# CANdiy-FD-Shield_v11.net
KiCad netlist of a schematic drawn in EAGLE
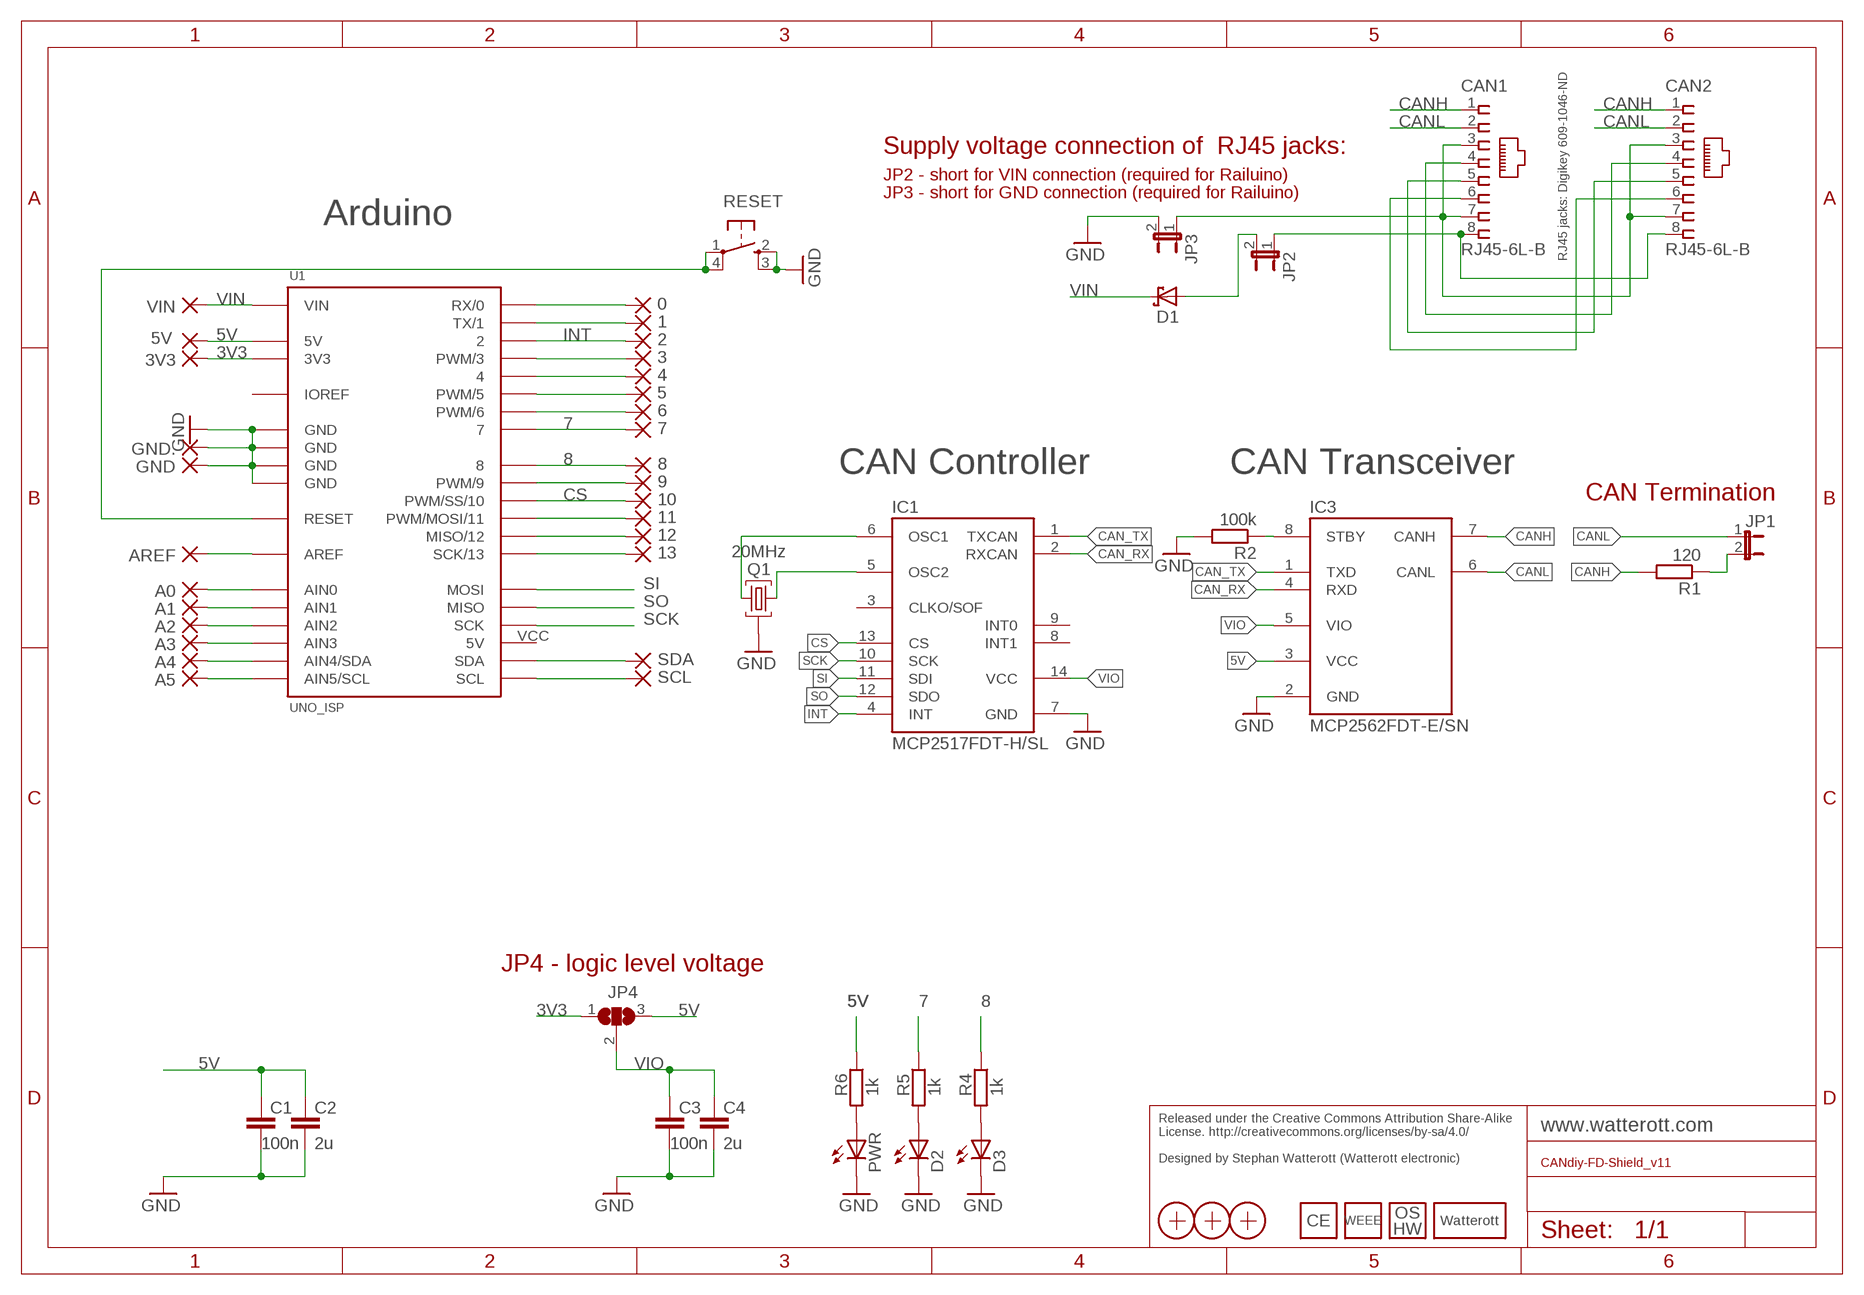
[diagram p0: schematic, sheet 1]

(export (version "E")
  (design (tool "Eeschema 10.0.6"))
  (components
    (comp (ref "0")
      (value "1,6/0,8")
      (footprint "eagle-import:1,6_0,8")
      (libsource (lib "eagle-import") (part "1,6/0,8"))
    )
    (comp (ref "1")
      (value "1,6/0,8")
      (footprint "eagle-import:1,6_0,8")
      (libsource (lib "eagle-import") (part "1,6/0,8"))
    )
    (comp (ref "2")
      (value "1,6/0,8")
      (footprint "eagle-import:1,6_0,8")
      (libsource (lib "eagle-import") (part "1,6/0,8"))
    )
    (comp (ref "3")
      (value "1,6/0,8")
      (footprint "eagle-import:1,6_0,8")
      (libsource (lib "eagle-import") (part "1,6/0,8"))
    )
    (comp (ref "3V3")
      (value "1,6/0,8")
      (footprint "eagle-import:1,6_0,8")
      (libsource (lib "eagle-import") (part "1,6/0,8"))
    )
    (comp (ref "4")
      (value "1,6/0,8")
      (footprint "eagle-import:1,6_0,8")
      (libsource (lib "eagle-import") (part "1,6/0,8"))
    )
    (comp (ref "5")
      (value "1,6/0,8")
      (footprint "eagle-import:1,6_0,8")
      (libsource (lib "eagle-import") (part "1,6/0,8"))
    )
    (comp (ref "5V")
      (value "1,6/0,8")
      (footprint "eagle-import:1,6_0,8")
      (libsource (lib "eagle-import") (part "1,6/0,8"))
    )
    (comp (ref "6")
      (value "1,6/0,8")
      (footprint "eagle-import:1,6_0,8")
      (libsource (lib "eagle-import") (part "1,6/0,8"))
    )
    (comp (ref "7")
      (value "1,6/0,8")
      (footprint "eagle-import:1,6_0,8")
      (libsource (lib "eagle-import") (part "1,6/0,8"))
    )
    (comp (ref "8")
      (value "1,6/0,8")
      (footprint "eagle-import:1,6_0,8")
      (libsource (lib "eagle-import") (part "1,6/0,8"))
    )
    (comp (ref "9")
      (value "1,6/0,8")
      (footprint "eagle-import:1,6_0,8")
      (libsource (lib "eagle-import") (part "1,6/0,8"))
    )
    (comp (ref "10")
      (value "1,6/0,8")
      (footprint "eagle-import:1,6_0,8")
      (libsource (lib "eagle-import") (part "1,6/0,8"))
    )
    (comp (ref "11")
      (value "1,6/0,8")
      (footprint "eagle-import:1,6_0,8")
      (libsource (lib "eagle-import") (part "1,6/0,8"))
    )
    (comp (ref "12")
      (value "1,6/0,8")
      (footprint "eagle-import:1,6_0,8")
      (libsource (lib "eagle-import") (part "1,6/0,8"))
    )
    (comp (ref "13")
      (value "1,6/0,8")
      (footprint "eagle-import:1,6_0,8")
      (libsource (lib "eagle-import") (part "1,6/0,8"))
    )
    (comp (ref "A0")
      (value "1,6/0,8")
      (footprint "eagle-import:1,6_0,8")
      (libsource (lib "eagle-import") (part "1,6/0,8"))
    )
    (comp (ref "A1")
      (value "1,6/0,8")
      (footprint "eagle-import:1,6_0,8")
      (libsource (lib "eagle-import") (part "1,6/0,8"))
    )
    (comp (ref "A2")
      (value "1,6/0,8")
      (footprint "eagle-import:1,6_0,8")
      (libsource (lib "eagle-import") (part "1,6/0,8"))
    )
    (comp (ref "A3")
      (value "1,6/0,8")
      (footprint "eagle-import:1,6_0,8")
      (libsource (lib "eagle-import") (part "1,6/0,8"))
    )
    (comp (ref "A4")
      (value "1,6/0,8")
      (footprint "eagle-import:1,6_0,8")
      (libsource (lib "eagle-import") (part "1,6/0,8"))
    )
    (comp (ref "A5")
      (value "1,6/0,8")
      (footprint "eagle-import:1,6_0,8")
      (libsource (lib "eagle-import") (part "1,6/0,8"))
    )
    (comp (ref "AREF")
      (value "1,6/0,8")
      (footprint "eagle-import:1,6_0,8")
      (libsource (lib "eagle-import") (part "1,6/0,8"))
    )
    (comp (ref "C1")
      (value "100n")
      (footprint "eagle-import:C0402")
      (libsource (lib "eagle-import") (part "C-EUC0402"))
    )
    (comp (ref "C2")
      (value "2u")
      (footprint "eagle-import:C0402")
      (libsource (lib "eagle-import") (part "C-EUC0402"))
    )
    (comp (ref "C3")
      (value "100n")
      (footprint "eagle-import:C0402")
      (libsource (lib "eagle-import") (part "C-EUC0402"))
    )
    (comp (ref "C4")
      (value "2u")
      (footprint "eagle-import:C0402")
      (libsource (lib "eagle-import") (part "C-EUC0402"))
    )
    (comp (ref "CAN1")
      (value "RJ45-6L-B")
      (footprint "eagle-import:RJ45-NO-SHIELD")
      (libsource (lib "eagle-import") (part "RJ45-6L-B"))
    )
    (comp (ref "CAN2")
      (value "RJ45-6L-B")
      (footprint "eagle-import:RJ45-NO-SHIELD")
      (libsource (lib "eagle-import") (part "RJ45-6L-B"))
    )
    (comp (ref "D1")
      (value "D_SCHOTTKY-SOD323")
      (footprint "eagle-import:SOD323")
      (libsource (lib "eagle-import") (part "D_SCHOTTKY-SOD323"))
    )
    (comp (ref "D2")
      (value "LEDCHIPLED_0603")
      (footprint "eagle-import:CHIPLED_0603")
      (libsource (lib "eagle-import") (part "LEDCHIPLED_0603"))
    )
    (comp (ref "D3")
      (value "LEDCHIPLED_0603")
      (footprint "eagle-import:CHIPLED_0603")
      (libsource (lib "eagle-import") (part "LEDCHIPLED_0603"))
    )
    (comp (ref "GND")
      (value "1,6/0,8")
      (footprint "eagle-import:1,6_0,8")
      (libsource (lib "eagle-import") (part "1,6/0,8"))
    )
    (comp (ref "GND.")
      (value "1,6/0,8")
      (footprint "eagle-import:1,6_0,8")
      (libsource (lib "eagle-import") (part "1,6/0,8"))
    )
    (comp (ref "IC1")
      (value "MCP2517FDT-H/SL")
      (footprint "eagle-import:SO14")
      (libsource (lib "eagle-import") (part "MCP2517FDT-H/SL"))
    )
    (comp (ref "IC3")
      (value "MCP2562FDT-E/SN")
      (footprint "eagle-import:SO08")
      (libsource (lib "eagle-import") (part "MCP2562FDT-E/SN"))
    )
    (comp (ref "JP1")
      (value "JP1E")
      (footprint "eagle-import:JP1")
      (libsource (lib "eagle-import") (part "JP1E"))
    )
    (comp (ref "JP2")
      (value "JP1E")
      (footprint "eagle-import:JP1")
      (libsource (lib "eagle-import") (part "JP1E"))
    )
    (comp (ref "JP3")
      (value "JP1E")
      (footprint "eagle-import:JP1")
      (libsource (lib "eagle-import") (part "JP1E"))
    )
    (comp (ref "JP4")
      (value "SJ2W")
      (footprint "eagle-import:SJ_2")
      (libsource (lib "eagle-import") (part "SJ2W"))
    )
    (comp (ref "LOGO3")
      (value "LOGO-9")
      (footprint "eagle-import:LOGO_9MM")
      (libsource (lib "eagle-import") (part "LOGO-9"))
    )
    (comp (ref "LOGO4")
      (value "LOGO_CE-2")
      (footprint "eagle-import:CE_2MM")
      (libsource (lib "eagle-import") (part "LOGO_CE-2"))
    )
    (comp (ref "LOGO5")
      (value "LOGO_OSHW-3")
      (footprint "eagle-import:OSHW_3MM")
      (libsource (lib "eagle-import") (part "LOGO_OSHW-3"))
    )
    (comp (ref "LOGO6")
      (value "LOGO_WEEE-4")
      (footprint "eagle-import:WEEE_4MM")
      (libsource (lib "eagle-import") (part "LOGO_WEEE-4"))
    )
    (comp (ref "PWR")
      (value "LEDCHIPLED_0603")
      (footprint "eagle-import:CHIPLED_0603")
      (libsource (lib "eagle-import") (part "LEDCHIPLED_0603"))
    )
    (comp (ref "Q1")
      (value "20MHz")
      (footprint "eagle-import:CRYSTAL_32X13")
      (libsource (lib "eagle-import") (part "CRYSTAL-RES-32"))
    )
    (comp (ref "R1")
      (value "120")
      (footprint "eagle-import:R0603")
      (libsource (lib "eagle-import") (part "resistor_R-EU_R0603"))
    )
    (comp (ref "R2")
      (value "100k")
      (footprint "eagle-import:R0402")
      (libsource (lib "eagle-import") (part "resistor_R-EU_R0402"))
    )
    (comp (ref "R4")
      (value "1k")
      (footprint "eagle-import:R0402")
      (libsource (lib "eagle-import") (part "R-EU_R0402"))
    )
    (comp (ref "R5")
      (value "1k")
      (footprint "eagle-import:R0402")
      (libsource (lib "eagle-import") (part "R-EU_R0402"))
    )
    (comp (ref "R6")
      (value "1k")
      (footprint "eagle-import:R0402")
      (libsource (lib "eagle-import") (part "R-EU_R0402"))
    )
    (comp (ref "RESET")
      (value "SW_SMDS")
      (footprint "eagle-import:SW_SMD4")
      (libsource (lib "eagle-import") (part "SW_SMDS"))
    )
    (comp (ref "SCL")
      (value "1,6/0,8")
      (footprint "eagle-import:1,6_0,8")
      (libsource (lib "eagle-import") (part "1,6/0,8"))
    )
    (comp (ref "SDA")
      (value "1,6/0,8")
      (footprint "eagle-import:1,6_0,8")
      (libsource (lib "eagle-import") (part "1,6/0,8"))
    )
    (comp (ref "U1")
      (value "UNO_ISP")
      (footprint "eagle-import:UNO_ISP")
      (libsource (lib "eagle-import") (part "UNO_ISP"))
    )
    (comp (ref "VIN")
      (value "1,6/0,8")
      (footprint "eagle-import:1,6_0,8")
      (libsource (lib "eagle-import") (part "1,6/0,8"))
    )
    (comp (ref "X1")
      (value "PASSER-07")
      (footprint "eagle-import:PASSER_07MM")
      (libsource (lib "eagle-import") (part "PASSER-07"))
    )
    (comp (ref "X2")
      (value "PASSER-07")
      (footprint "eagle-import:PASSER_07MM")
      (libsource (lib "eagle-import") (part "PASSER-07"))
    )
    (comp (ref "X3")
      (value "PASSER-07")
      (footprint "eagle-import:PASSER_07MM")
      (libsource (lib "eagle-import") (part "PASSER-07"))
    )
  )
  (nets
    (net (code "1") (name "/3V3") (class "Default")
      (node (ref "3V3") (pin "1") (pinfunction "P_1") (pintype "passive"))
      (node (ref "JP4") (pin "1") (pinfunction "1_1") (pintype "passive"))
      (node (ref "U1") (pin "3V3") (pinfunction "3V3_3V3") (pintype "power_in"))
    )
    (net (code "2") (name "/7") (class "Default")
      (node (ref "7") (pin "1") (pinfunction "P_1") (pintype "passive"))
      (node (ref "R5") (pin "1") (pinfunction "1_1") (pintype "passive"))
      (node (ref "U1") (pin "7") (pinfunction "7_7") (pintype "bidirectional"))
    )
    (net (code "3") (name "/8") (class "Default")
      (node (ref "8") (pin "1") (pinfunction "P_1") (pintype "passive"))
      (node (ref "R4") (pin "1") (pinfunction "1_1") (pintype "passive"))
      (node (ref "U1") (pin "8") (pinfunction "8_8") (pintype "bidirectional"))
    )
    (net (code "4") (name "/IOREF") (class "Default")
      (node (ref "U1") (pin "IOREF") (pinfunction "IOREF_IOREF") (pintype "power_in"))
    )
    (net (code "5") (name "/VIN") (class "Default")
      (node (ref "D1") (pin "C") (pinfunction "C_C") (pintype "passive"))
      (node (ref "U1") (pin "VIN") (pinfunction "VIN_VIN") (pintype "power_in"))
      (node (ref "VIN") (pin "1") (pinfunction "P_1") (pintype "passive"))
    )
    (net (code "6") (name "5V") (class "Default")
      (node (ref "5V") (pin "1") (pinfunction "P_1") (pintype "passive"))
      (node (ref "C1") (pin "1") (pinfunction "1_1") (pintype "passive"))
      (node (ref "C2") (pin "1") (pinfunction "1_1") (pintype "passive"))
      (node (ref "IC3") (pin "3") (pinfunction "VCC_3") (pintype "power_in"))
      (node (ref "JP4") (pin "3") (pinfunction "3_3") (pintype "passive"))
      (node (ref "R6") (pin "1") (pinfunction "1_1") (pintype "passive"))
      (node (ref "U1") (pin "5V") (pinfunction "5V_5V") (pintype "power_in"))
    )
    (net (code "7") (name "CANH") (class "Default")
      (node (ref "CAN1") (pin "1") (pinfunction "1_1") (pintype "passive"))
      (node (ref "CAN2") (pin "1") (pinfunction "1_1") (pintype "passive"))
      (node (ref "IC3") (pin "7") (pinfunction "CANH_7") (pintype "passive"))
      (node (ref "R1") (pin "2") (pinfunction "2_2") (pintype "passive"))
    )
    (net (code "8") (name "CANL") (class "Default")
      (node (ref "CAN1") (pin "2") (pinfunction "2_2") (pintype "passive"))
      (node (ref "CAN2") (pin "2") (pinfunction "2_2") (pintype "passive"))
      (node (ref "IC3") (pin "6") (pinfunction "CANL_6") (pintype "passive"))
      (node (ref "JP1") (pin "1") (pinfunction "1_1") (pintype "passive"))
    )
    (net (code "9") (name "CAN_RX") (class "Default")
      (node (ref "IC1") (pin "2") (pinfunction "RXCAN_2") (pintype "bidirectional"))
      (node (ref "IC3") (pin "4") (pinfunction "RXD_4") (pintype "bidirectional"))
    )
    (net (code "10") (name "CAN_TX") (class "Default")
      (node (ref "IC1") (pin "1") (pinfunction "TXCAN_1") (pintype "bidirectional"))
      (node (ref "IC3") (pin "1") (pinfunction "TXD_1") (pintype "bidirectional"))
    )
    (net (code "11") (name "CS") (class "Default")
      (node (ref "10") (pin "1") (pinfunction "P_1") (pintype "passive"))
      (node (ref "IC1") (pin "13") (pinfunction "CS_13") (pintype "bidirectional"))
      (node (ref "U1") (pin "10") (pinfunction "PWM/SS/10_10") (pintype "bidirectional"))
    )
    (net (code "12") (name "GND") (class "Default")
      (node (ref "C1") (pin "2") (pinfunction "2_2") (pintype "passive"))
      (node (ref "C2") (pin "2") (pinfunction "2_2") (pintype "passive"))
      (node (ref "C3") (pin "2") (pinfunction "2_2") (pintype "passive"))
      (node (ref "C4") (pin "2") (pinfunction "2_2") (pintype "passive"))
      (node (ref "D2") (pin "C") (pinfunction "C_C") (pintype "passive"))
      (node (ref "D3") (pin "C") (pinfunction "C_C") (pintype "passive"))
      (node (ref "GND") (pin "1") (pinfunction "P_1") (pintype "passive"))
      (node (ref "GND.") (pin "1") (pinfunction "P_1") (pintype "passive"))
      (node (ref "IC1") (pin "7") (pinfunction "GND_7") (pintype "power_in"))
      (node (ref "IC3") (pin "2") (pinfunction "GND_2") (pintype "power_in"))
      (node (ref "JP3") (pin "2") (pinfunction "2_2") (pintype "passive"))
      (node (ref "PWR") (pin "C") (pinfunction "C_C") (pintype "passive"))
      (node (ref "Q1") (pin "GND") (pinfunction "GND_GND") (pintype "passive"))
      (node (ref "R2") (pin "2") (pinfunction "2_2") (pintype "passive"))
      (node (ref "RESET") (pin "2") (pinfunction "S_2") (pintype "passive"))
      (node (ref "RESET") (pin "3") (pinfunction "S1_3") (pintype "passive"))
      (node (ref "U1") (pin "GND@1") (pinfunction "GND_GND@1") (pintype "power_in"))
      (node (ref "U1") (pin "GND@2") (pinfunction "GND_GND@2") (pintype "power_in"))
      (node (ref "U1") (pin "GND@3") (pinfunction "GND_GND@3") (pintype "power_in"))
      (node (ref "U1") (pin "GND@4") (pinfunction "GND_GND@4") (pintype "power_in"))
    )
    (net (code "13") (name "INT") (class "Default")
      (node (ref "2") (pin "1") (pinfunction "P_1") (pintype "passive"))
      (node (ref "IC1") (pin "4") (pinfunction "INT_4") (pintype "bidirectional"))
      (node (ref "U1") (pin "2") (pinfunction "2_2") (pintype "bidirectional"))
    )
    (net (code "14") (name "Net-(0-P)") (class "Default")
      (node (ref "0") (pin "1") (pinfunction "P_1") (pintype "passive"))
      (node (ref "U1") (pin "0") (pinfunction "RX/0_0") (pintype "bidirectional"))
    )
    (net (code "15") (name "Net-(1-P)") (class "Default")
      (node (ref "1") (pin "1") (pinfunction "P_1") (pintype "passive"))
      (node (ref "U1") (pin "1") (pinfunction "TX/1_1") (pintype "bidirectional"))
    )
    (net (code "16") (name "Net-(3-P)") (class "Default")
      (node (ref "3") (pin "1") (pinfunction "P_1") (pintype "passive"))
      (node (ref "U1") (pin "3") (pinfunction "PWM/3_3") (pintype "bidirectional"))
    )
    (net (code "17") (name "Net-(4-P)") (class "Default")
      (node (ref "4") (pin "1") (pinfunction "P_1") (pintype "passive"))
      (node (ref "U1") (pin "4") (pinfunction "4_4") (pintype "bidirectional"))
    )
    (net (code "18") (name "Net-(5-P)") (class "Default")
      (node (ref "5") (pin "1") (pinfunction "P_1") (pintype "passive"))
      (node (ref "U1") (pin "5") (pinfunction "PWM/5_5") (pintype "bidirectional"))
    )
    (net (code "19") (name "Net-(6-P)") (class "Default")
      (node (ref "6") (pin "1") (pinfunction "P_1") (pintype "passive"))
      (node (ref "U1") (pin "6") (pinfunction "PWM/6_6") (pintype "bidirectional"))
    )
    (net (code "20") (name "Net-(9-P)") (class "Default")
      (node (ref "9") (pin "1") (pinfunction "P_1") (pintype "passive"))
      (node (ref "U1") (pin "9") (pinfunction "PWM/9_9") (pintype "bidirectional"))
    )
    (net (code "21") (name "Net-(11-P)") (class "Default")
      (node (ref "11") (pin "1") (pinfunction "P_1") (pintype "passive"))
      (node (ref "U1") (pin "11") (pinfunction "PWM/MOSI/11_11") (pintype "bidirectional"))
    )
    (net (code "22") (name "Net-(12-P)") (class "Default")
      (node (ref "12") (pin "1") (pinfunction "P_1") (pintype "passive"))
      (node (ref "U1") (pin "12") (pinfunction "MISO/12_12") (pintype "bidirectional"))
    )
    (net (code "23") (name "Net-(13-P)") (class "Default")
      (node (ref "13") (pin "1") (pinfunction "P_1") (pintype "passive"))
      (node (ref "U1") (pin "13") (pinfunction "SCK/13_13") (pintype "bidirectional"))
    )
    (net (code "24") (name "Net-(A0-P)") (class "Default")
      (node (ref "A0") (pin "1") (pinfunction "P_1") (pintype "passive"))
      (node (ref "U1") (pin "AIN0") (pinfunction "AIN0_AIN0") (pintype "bidirectional"))
    )
    (net (code "25") (name "Net-(A1-P)") (class "Default")
      (node (ref "A1") (pin "1") (pinfunction "P_1") (pintype "passive"))
      (node (ref "U1") (pin "AIN1") (pinfunction "AIN1_AIN1") (pintype "bidirectional"))
    )
    (net (code "26") (name "Net-(A2-P)") (class "Default")
      (node (ref "A2") (pin "1") (pinfunction "P_1") (pintype "passive"))
      (node (ref "U1") (pin "AIN2") (pinfunction "AIN2_AIN2") (pintype "bidirectional"))
    )
    (net (code "27") (name "Net-(A3-P)") (class "Default")
      (node (ref "A3") (pin "1") (pinfunction "P_1") (pintype "passive"))
      (node (ref "U1") (pin "AIN3") (pinfunction "AIN3_AIN3") (pintype "bidirectional"))
    )
    (net (code "28") (name "Net-(A4-P)") (class "Default")
      (node (ref "A4") (pin "1") (pinfunction "P_1") (pintype "passive"))
      (node (ref "U1") (pin "AIN4") (pinfunction "AIN4/SDA_AIN4") (pintype "bidirectional"))
    )
    (net (code "29") (name "Net-(A5-P)") (class "Default")
      (node (ref "A5") (pin "1") (pinfunction "P_1") (pintype "passive"))
      (node (ref "U1") (pin "AIN5") (pinfunction "AIN5/SCL_AIN5") (pintype "bidirectional"))
    )
    (net (code "30") (name "Net-(AREF-P)") (class "Default")
      (node (ref "AREF") (pin "1") (pinfunction "P_1") (pintype "passive"))
      (node (ref "U1") (pin "AREF") (pinfunction "AREF_AREF") (pintype "power_in"))
    )
    (net (code "31") (name "Net-(CAN1-Pad3)") (class "Default")
      (node (ref "CAN1") (pin "3") (pinfunction "3_3") (pintype "passive"))
      (node (ref "CAN1") (pin "7") (pinfunction "7_7") (pintype "passive"))
      (node (ref "CAN2") (pin "3") (pinfunction "3_3") (pintype "passive"))
      (node (ref "CAN2") (pin "7") (pinfunction "7_7") (pintype "passive"))
      (node (ref "JP3") (pin "1") (pinfunction "1_1") (pintype "passive"))
    )
    (net (code "32") (name "Net-(CAN1-Pad4)") (class "Default")
      (node (ref "CAN1") (pin "4") (pinfunction "4_4") (pintype "passive"))
      (node (ref "CAN2") (pin "4") (pinfunction "4_4") (pintype "passive"))
    )
    (net (code "33") (name "Net-(CAN1-Pad5)") (class "Default")
      (node (ref "CAN1") (pin "5") (pinfunction "5_5") (pintype "passive"))
      (node (ref "CAN2") (pin "5") (pinfunction "5_5") (pintype "passive"))
    )
    (net (code "34") (name "Net-(CAN1-Pad6)") (class "Default")
      (node (ref "CAN1") (pin "6") (pinfunction "6_6") (pintype "passive"))
      (node (ref "CAN2") (pin "6") (pinfunction "6_6") (pintype "passive"))
    )
    (net (code "35") (name "Net-(CAN1-Pad8)") (class "Default")
      (node (ref "CAN1") (pin "8") (pinfunction "8_8") (pintype "passive"))
      (node (ref "CAN2") (pin "8") (pinfunction "8_8") (pintype "passive"))
      (node (ref "JP2") (pin "1") (pinfunction "1_1") (pintype "passive"))
    )
    (net (code "36") (name "Net-(D1-PadA)") (class "Default")
      (node (ref "D1") (pin "A") (pinfunction "A_A") (pintype "passive"))
      (node (ref "JP2") (pin "2") (pinfunction "2_2") (pintype "passive"))
    )
    (net (code "37") (name "Net-(D2-PadA)") (class "Default")
      (node (ref "D2") (pin "A") (pinfunction "A_A") (pintype "passive"))
      (node (ref "R5") (pin "2") (pinfunction "2_2") (pintype "passive"))
    )
    (net (code "38") (name "Net-(D3-PadA)") (class "Default")
      (node (ref "D3") (pin "A") (pinfunction "A_A") (pintype "passive"))
      (node (ref "R4") (pin "2") (pinfunction "2_2") (pintype "passive"))
    )
    (net (code "39") (name "Net-(IC1-OSC1)") (class "Default")
      (node (ref "IC1") (pin "6") (pinfunction "OSC1_6") (pintype "bidirectional"))
      (node (ref "Q1") (pin "2") (pinfunction "2_2") (pintype "passive"))
    )
    (net (code "40") (name "Net-(IC1-OSC2)") (class "Default")
      (node (ref "IC1") (pin "5") (pinfunction "OSC2_5") (pintype "bidirectional"))
      (node (ref "Q1") (pin "1") (pinfunction "1_1") (pintype "passive"))
    )
    (net (code "41") (name "Net-(IC3-STBY)") (class "Default")
      (node (ref "IC3") (pin "8") (pinfunction "STBY_8") (pintype "bidirectional"))
      (node (ref "R2") (pin "1") (pinfunction "1_1") (pintype "passive"))
    )
    (net (code "42") (name "Net-(JP1-Pad2)") (class "Default")
      (node (ref "JP1") (pin "2") (pinfunction "2_2") (pintype "passive"))
      (node (ref "R1") (pin "1") (pinfunction "1_1") (pintype "passive"))
    )
    (net (code "43") (name "Net-(PWR-PadA)") (class "Default")
      (node (ref "PWR") (pin "A") (pinfunction "A_A") (pintype "passive"))
      (node (ref "R6") (pin "2") (pinfunction "2_2") (pintype "passive"))
    )
    (net (code "44") (name "Net-(RESET-P)") (class "Default")
      (node (ref "RESET") (pin "1") (pinfunction "P_1") (pintype "passive"))
      (node (ref "RESET") (pin "4") (pinfunction "P1_4") (pintype "passive"))
      (node (ref "U1") (pin "RST") (pinfunction "RESET_RST") (pintype "bidirectional"))
    )
    (net (code "45") (name "Net-(SCL-P)") (class "Default")
      (node (ref "SCL") (pin "1") (pinfunction "P_1") (pintype "passive"))
      (node (ref "U1") (pin "SCL") (pinfunction "SCL_SCL") (pintype "bidirectional"))
    )
    (net (code "46") (name "Net-(SDA-P)") (class "Default")
      (node (ref "SDA") (pin "1") (pinfunction "P_1") (pintype "passive"))
      (node (ref "U1") (pin "SDA") (pinfunction "SDA_SDA") (pintype "bidirectional"))
    )
    (net (code "47") (name "SCK") (class "Default")
      (node (ref "IC1") (pin "10") (pinfunction "SCK_10") (pintype "bidirectional"))
      (node (ref "U1") (pin "SCK") (pinfunction "SCK_SCK") (pintype "bidirectional"))
    )
    (net (code "48") (name "SI") (class "Default")
      (node (ref "IC1") (pin "11") (pinfunction "SDI_11") (pintype "bidirectional"))
      (node (ref "U1") (pin "MOSI") (pinfunction "MOSI_MOSI") (pintype "bidirectional"))
    )
    (net (code "49") (name "SO") (class "Default")
      (node (ref "IC1") (pin "12") (pinfunction "SDO_12") (pintype "bidirectional"))
      (node (ref "U1") (pin "MISO") (pinfunction "MISO_MISO") (pintype "bidirectional"))
    )
    (net (code "50") (name "VIO") (class "Default")
      (node (ref "C3") (pin "1") (pinfunction "1_1") (pintype "passive"))
      (node (ref "C4") (pin "1") (pinfunction "1_1") (pintype "passive"))
      (node (ref "IC1") (pin "14") (pinfunction "VCC_14") (pintype "power_in"))
      (node (ref "IC3") (pin "5") (pinfunction "VIO_5") (pintype "power_in"))
      (node (ref "JP4") (pin "2") (pinfunction "2_2") (pintype "passive"))
    )
    (net (code "51") (name "unconnected-(IC1-CLKO{slash}SOF-Pad3)") (class "Default")
      (node (ref "IC1") (pin "3") (pinfunction "CLKO/SOF_3") (pintype "bidirectional"))
    )
    (net (code "52") (name "unconnected-(IC1-INT0-Pad9)") (class "Default")
      (node (ref "IC1") (pin "9") (pinfunction "INT0_9") (pintype "bidirectional"))
    )
    (net (code "53") (name "unconnected-(IC1-INT1-Pad8)") (class "Default")
      (node (ref "IC1") (pin "8") (pinfunction "INT1_8") (pintype "bidirectional"))
    )
    (net (code "54") (name "unconnected-(U1-5V-PadVCC)") (class "Default")
      (node (ref "U1") (pin "VCC") (pinfunction "5V_VCC") (pintype "bidirectional"))
    )
  )
)
